# mdriver.net
KiCad netlist of a schematic drawn in Altium Designer
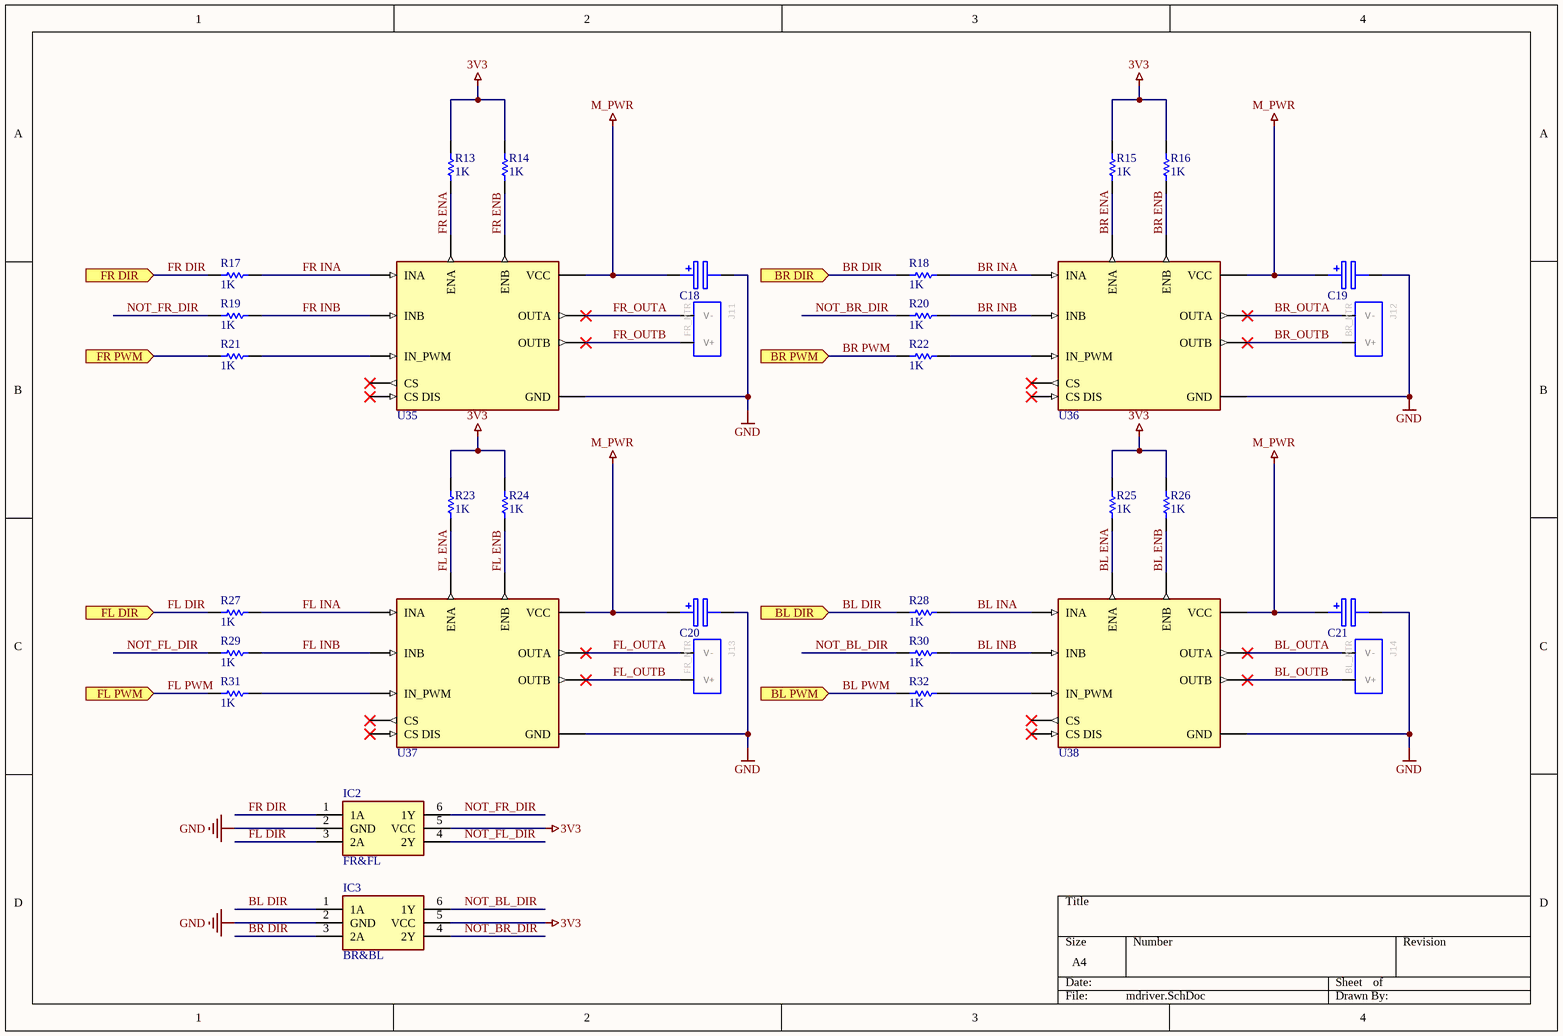
[diagram p0: mdriver.SchDoc]

(export (version "E")
  (design (tool "Eeschema 10.0.6"))
  (components
    (comp (ref "C18")
      (value "47u")
      (footprint "EEE0JA331XP")
      (description "Cap Aluminum Lytic 47uF 50V 20% (6.3 X 7.7mm) SMD 63mA 2000h 105C Automotive T/R")
      (fields
        (field (name "MOUSER PART NUMBER") "667-EEE-HBH470YAP")
        (field (name "ARROW PART NUMBER") "EEE-HBH470YAP")
      )
      (libsource (lib "Hwa Chong Institution") (part "EEE-HBH470YAP"))
    )
    (comp (ref "C19")
      (value "47u")
      (footprint "EEE0JA331XP")
      (description "Cap Aluminum Lytic 47uF 50V 20% (6.3 X 7.7mm) SMD 63mA 2000h 105C Automotive T/R")
      (fields
        (field (name "MOUSER PART NUMBER") "667-EEE-HBH470YAP")
        (field (name "ARROW PART NUMBER") "EEE-HBH470YAP")
      )
      (libsource (lib "Hwa Chong Institution") (part "EEE-HBH470YAP"))
    )
    (comp (ref "C20")
      (value "47u")
      (footprint "EEE0JA331XP")
      (description "Cap Aluminum Lytic 47uF 50V 20% (6.3 X 7.7mm) SMD 63mA 2000h 105C Automotive T/R")
      (fields
        (field (name "MOUSER PART NUMBER") "667-EEE-HBH470YAP")
        (field (name "ARROW PART NUMBER") "EEE-HBH470YAP")
      )
      (libsource (lib "Hwa Chong Institution") (part "EEE-HBH470YAP"))
    )
    (comp (ref "C21")
      (value "47u")
      (footprint "EEE0JA331XP")
      (description "Cap Aluminum Lytic 47uF 50V 20% (6.3 X 7.7mm) SMD 63mA 2000h 105C Automotive T/R")
      (fields
        (field (name "MOUSER PART NUMBER") "667-EEE-HBH470YAP")
        (field (name "ARROW PART NUMBER") "EEE-HBH470YAP")
      )
      (libsource (lib "Hwa Chong Institution") (part "EEE-HBH470YAP"))
    )
    (comp (ref "IC2")
      (value "FR&FL")
      (footprint "SOT-23-6")
      (description "Integrated Circuit")
      (fields
        (field (name "MOUSER PART NUMBER") "595-SN74LVC2G04DRLR")
        (field (name "MANUFACTURER_PART_NUMBER") "SN74LVC2G04DRLR")
      )
      (libsource (lib "Integrated_Library1") (part "SN74LVC2G04DRLR"))
    )
    (comp (ref "IC3")
      (value "BR&BL")
      (footprint "SOT-23-6")
      (description "Integrated Circuit")
      (fields
        (field (name "MOUSER PART NUMBER") "595-SN74LVC2G04DRLR")
        (field (name "MANUFACTURER_PART_NUMBER") "SN74LVC2G04DRLR")
      )
      (libsource (lib "Integrated_Library1") (part "SN74LVC2G04DRLR"))
    )
    (comp (ref "J11")
      (value "FR_MTR")
      (footprint "XT30PB-F")
      (libsource (lib "Integrated_Library1") (part "XT30PB-F"))
    )
    (comp (ref "J12")
      (value "BR_MTR")
      (footprint "XT30PB-F")
      (libsource (lib "Integrated_Library1") (part "XT30PB-F"))
    )
    (comp (ref "J13")
      (value "FR_MTR")
      (footprint "XT30PB-F")
      (libsource (lib "Integrated_Library1") (part "XT30PB-F"))
    )
    (comp (ref "J14")
      (value "BL_MTR")
      (footprint "XT30PB-F")
      (libsource (lib "Integrated_Library1") (part "XT30PB-F"))
    )
    (comp (ref "R13")
      (value "1K")
      (footprint "RES0603")
      (description "Resistor")
      (libsource (lib "Integrated_Library1") (part "RES0603"))
    )
    (comp (ref "R14")
      (value "1K")
      (footprint "RES0603")
      (description "Resistor")
      (libsource (lib "Integrated_Library1") (part "RES0603"))
    )
    (comp (ref "R15")
      (value "1K")
      (footprint "RES0603")
      (description "Resistor")
      (libsource (lib "Integrated_Library1") (part "RES0603"))
    )
    (comp (ref "R16")
      (value "1K")
      (footprint "RES0603")
      (description "Resistor")
      (libsource (lib "Integrated_Library1") (part "RES0603"))
    )
    (comp (ref "R17")
      (value "1K")
      (footprint "RES0603")
      (description "Resistor")
      (libsource (lib "Integrated_Library1") (part "RES0603"))
    )
    (comp (ref "R18")
      (value "1K")
      (footprint "RES0603")
      (description "Resistor")
      (libsource (lib "Integrated_Library1") (part "RES0603"))
    )
    (comp (ref "R19")
      (value "1K")
      (footprint "RES0603")
      (description "Resistor")
      (libsource (lib "Integrated_Library1") (part "RES0603"))
    )
    (comp (ref "R20")
      (value "1K")
      (footprint "RES0603")
      (description "Resistor")
      (libsource (lib "Integrated_Library1") (part "RES0603"))
    )
    (comp (ref "R21")
      (value "1K")
      (footprint "RES0603")
      (description "Resistor")
      (libsource (lib "Integrated_Library1") (part "RES0603"))
    )
    (comp (ref "R22")
      (value "1K")
      (footprint "RES0603")
      (description "Resistor")
      (libsource (lib "Integrated_Library1") (part "RES0603"))
    )
    (comp (ref "R23")
      (value "1K")
      (footprint "RES0603")
      (description "Resistor")
      (libsource (lib "Integrated_Library1") (part "RES0603"))
    )
    (comp (ref "R24")
      (value "1K")
      (footprint "RES0603")
      (description "Resistor")
      (libsource (lib "Integrated_Library1") (part "RES0603"))
    )
    (comp (ref "R25")
      (value "1K")
      (footprint "RES0603")
      (description "Resistor")
      (libsource (lib "Integrated_Library1") (part "RES0603"))
    )
    (comp (ref "R26")
      (value "1K")
      (footprint "RES0603")
      (description "Resistor")
      (libsource (lib "Integrated_Library1") (part "RES0603"))
    )
    (comp (ref "R27")
      (value "1K")
      (footprint "RES0603")
      (description "Resistor")
      (libsource (lib "Integrated_Library1") (part "RES0603"))
    )
    (comp (ref "R28")
      (value "1K")
      (footprint "RES0603")
      (description "Resistor")
      (libsource (lib "Integrated_Library1") (part "RES0603"))
    )
    (comp (ref "R29")
      (value "1K")
      (footprint "RES0603")
      (description "Resistor")
      (libsource (lib "Integrated_Library1") (part "RES0603"))
    )
    (comp (ref "R30")
      (value "1K")
      (footprint "RES0603")
      (description "Resistor")
      (libsource (lib "Integrated_Library1") (part "RES0603"))
    )
    (comp (ref "R31")
      (value "1K")
      (footprint "RES0603")
      (description "Resistor")
      (libsource (lib "Integrated_Library1") (part "RES0603"))
    )
    (comp (ref "R32")
      (value "1K")
      (footprint "RES0603")
      (description "Resistor")
      (libsource (lib "Integrated_Library1") (part "RES0603"))
    )
    (comp (ref "U35")
      (value "FR")
      (footprint "SOP50P1030X247-39N")
      (description "Motor Driver Power MOSFET Parallel, PWM PowerSSO-36")
      (fields (field (name "MF") "STMicroelectronics") (field (name "MP") "VNH5050A-E"))
      (libsource (lib "Integrated_Library1") (part "VNH5050A-E"))
    )
    (comp (ref "U36")
      (value "BR")
      (footprint "SOP50P1030X247-39N")
      (description "Motor Driver Power MOSFET Parallel, PWM PowerSSO-36")
      (fields (field (name "MF") "STMicroelectronics") (field (name "MP") "VNH5050A-E"))
      (libsource (lib "Integrated_Library1") (part "VNH5050A-E"))
    )
    (comp (ref "U37")
      (value "FL")
      (footprint "SOP50P1030X247-39N")
      (description "Motor Driver Power MOSFET Parallel, PWM PowerSSO-36")
      (fields (field (name "MF") "STMicroelectronics") (field (name "MP") "VNH5050A-E"))
      (libsource (lib "Integrated_Library1") (part "VNH5050A-E"))
    )
    (comp (ref "U38")
      (value "BL")
      (footprint "SOP50P1030X247-39N")
      (description "Motor Driver Power MOSFET Parallel, PWM PowerSSO-36")
      (fields (field (name "MF") "STMicroelectronics") (field (name "MP") "VNH5050A-E"))
      (libsource (lib "Integrated_Library1") (part "VNH5050A-E"))
    )
  )
  (nets
    (net (code "1") (name "/BL DIR") (class "Default")
      (node (ref "IC3") (pin "1") (pinfunction "1A_1") (pintype "passive"))
      (node (ref "R28") (pin "2") (pinfunction "2_2") (pintype "passive"))
    )
    (net (code "2") (name "/BL ENA") (class "Default")
      (node (ref "R25") (pin "1") (pinfunction "1_1") (pintype "passive"))
      (node (ref "U38") (pin "16") (pinfunction "ENA_16") (pintype "output"))
    )
    (net (code "3") (name "/BL ENB") (class "Default")
      (node (ref "R26") (pin "1") (pinfunction "1_1") (pintype "passive"))
      (node (ref "U38") (pin "21") (pinfunction "ENB_21") (pintype "output"))
    )
    (net (code "4") (name "/BL INA") (class "Default")
      (node (ref "R28") (pin "1") (pinfunction "1_1") (pintype "passive"))
      (node (ref "U38") (pin "15") (pinfunction "INA_15") (pintype "input"))
    )
    (net (code "5") (name "/BL INB") (class "Default")
      (node (ref "R30") (pin "1") (pinfunction "1_1") (pintype "passive"))
      (node (ref "U38") (pin "22") (pinfunction "INB_22") (pintype "input"))
    )
    (net (code "6") (name "/BL PWM") (class "Default")
      (node (ref "R32") (pin "2") (pinfunction "2_2") (pintype "passive"))
    )
    (net (code "7") (name "/BL_OUTA") (class "Default")
      (node (ref "J14") (pin "-") (pinfunction "V-_-") (pintype "power_in"))
      (node (ref "U38") (pin "38") (pinfunction "OUTA_38") (pintype "output"))
    )
    (net (code "8") (name "/BL_OUTB") (class "Default")
      (node (ref "J14") (pin "+") (pinfunction "V+_+") (pintype "power_in"))
      (node (ref "U38") (pin "37") (pinfunction "OUTB_37") (pintype "output"))
    )
    (net (code "9") (name "/BR DIR") (class "Default")
      (node (ref "IC3") (pin "3") (pinfunction "2A_3") (pintype "passive"))
      (node (ref "R18") (pin "2") (pinfunction "2_2") (pintype "passive"))
    )
    (net (code "10") (name "/BR ENA") (class "Default")
      (node (ref "R15") (pin "1") (pinfunction "1_1") (pintype "passive"))
      (node (ref "U36") (pin "16") (pinfunction "ENA_16") (pintype "output"))
    )
    (net (code "11") (name "/BR ENB") (class "Default")
      (node (ref "R16") (pin "1") (pinfunction "1_1") (pintype "passive"))
      (node (ref "U36") (pin "21") (pinfunction "ENB_21") (pintype "output"))
    )
    (net (code "12") (name "/BR INA") (class "Default")
      (node (ref "R18") (pin "1") (pinfunction "1_1") (pintype "passive"))
      (node (ref "U36") (pin "15") (pinfunction "INA_15") (pintype "input"))
    )
    (net (code "13") (name "/BR INB") (class "Default")
      (node (ref "R20") (pin "1") (pinfunction "1_1") (pintype "passive"))
      (node (ref "U36") (pin "22") (pinfunction "INB_22") (pintype "input"))
    )
    (net (code "14") (name "/BR PWM") (class "Default")
      (node (ref "R22") (pin "2") (pinfunction "2_2") (pintype "passive"))
    )
    (net (code "15") (name "/BR_OUTA") (class "Default")
      (node (ref "J12") (pin "-") (pinfunction "V-_-") (pintype "power_in"))
      (node (ref "U36") (pin "38") (pinfunction "OUTA_38") (pintype "output"))
    )
    (net (code "16") (name "/BR_OUTB") (class "Default")
      (node (ref "J12") (pin "+") (pinfunction "V+_+") (pintype "power_in"))
      (node (ref "U36") (pin "37") (pinfunction "OUTB_37") (pintype "output"))
    )
    (net (code "17") (name "/FL DIR") (class "Default")
      (node (ref "IC2") (pin "3") (pinfunction "2A_3") (pintype "passive"))
      (node (ref "R27") (pin "2") (pinfunction "2_2") (pintype "passive"))
    )
    (net (code "18") (name "/FL ENA") (class "Default")
      (node (ref "R23") (pin "1") (pinfunction "1_1") (pintype "passive"))
      (node (ref "U37") (pin "16") (pinfunction "ENA_16") (pintype "output"))
    )
    (net (code "19") (name "/FL ENB") (class "Default")
      (node (ref "R24") (pin "1") (pinfunction "1_1") (pintype "passive"))
      (node (ref "U37") (pin "21") (pinfunction "ENB_21") (pintype "output"))
    )
    (net (code "20") (name "/FL INA") (class "Default")
      (node (ref "R27") (pin "1") (pinfunction "1_1") (pintype "passive"))
      (node (ref "U37") (pin "15") (pinfunction "INA_15") (pintype "input"))
    )
    (net (code "21") (name "/FL INB") (class "Default")
      (node (ref "R29") (pin "1") (pinfunction "1_1") (pintype "passive"))
      (node (ref "U37") (pin "22") (pinfunction "INB_22") (pintype "input"))
    )
    (net (code "22") (name "/FL PWM") (class "Default")
      (node (ref "R31") (pin "2") (pinfunction "2_2") (pintype "passive"))
    )
    (net (code "23") (name "/FL_OUTA") (class "Default")
      (node (ref "J13") (pin "-") (pinfunction "V-_-") (pintype "power_in"))
      (node (ref "U37") (pin "38") (pinfunction "OUTA_38") (pintype "output"))
    )
    (net (code "24") (name "/FL_OUTB") (class "Default")
      (node (ref "J13") (pin "+") (pinfunction "V+_+") (pintype "power_in"))
      (node (ref "U37") (pin "37") (pinfunction "OUTB_37") (pintype "output"))
    )
    (net (code "25") (name "/FR DIR") (class "Default")
      (node (ref "IC2") (pin "1") (pinfunction "1A_1") (pintype "passive"))
      (node (ref "R17") (pin "2") (pinfunction "2_2") (pintype "passive"))
    )
    (net (code "26") (name "/FR ENA") (class "Default")
      (node (ref "R13") (pin "1") (pinfunction "1_1") (pintype "passive"))
      (node (ref "U35") (pin "16") (pinfunction "ENA_16") (pintype "output"))
    )
    (net (code "27") (name "/FR ENB") (class "Default")
      (node (ref "R14") (pin "1") (pinfunction "1_1") (pintype "passive"))
      (node (ref "U35") (pin "21") (pinfunction "ENB_21") (pintype "output"))
    )
    (net (code "28") (name "/FR INA") (class "Default")
      (node (ref "R17") (pin "1") (pinfunction "1_1") (pintype "passive"))
      (node (ref "U35") (pin "15") (pinfunction "INA_15") (pintype "input"))
    )
    (net (code "29") (name "/FR INB") (class "Default")
      (node (ref "R19") (pin "1") (pinfunction "1_1") (pintype "passive"))
      (node (ref "U35") (pin "22") (pinfunction "INB_22") (pintype "input"))
    )
    (net (code "30") (name "/FR PWM") (class "Default")
      (node (ref "R21") (pin "2") (pinfunction "2_2") (pintype "passive"))
    )
    (net (code "31") (name "/FR_OUTA") (class "Default")
      (node (ref "J11") (pin "-") (pinfunction "V-_-") (pintype "power_in"))
      (node (ref "U35") (pin "38") (pinfunction "OUTA_38") (pintype "output"))
    )
    (net (code "32") (name "/FR_OUTB") (class "Default")
      (node (ref "J11") (pin "+") (pinfunction "V+_+") (pintype "power_in"))
      (node (ref "U35") (pin "37") (pinfunction "OUTB_37") (pintype "output"))
    )
    (net (code "33") (name "/NOT_BL_DIR") (class "Default")
      (node (ref "IC3") (pin "6") (pinfunction "1Y_6") (pintype "passive"))
      (node (ref "R30") (pin "2") (pinfunction "2_2") (pintype "passive"))
    )
    (net (code "34") (name "/NOT_BR_DIR") (class "Default")
      (node (ref "IC3") (pin "4") (pinfunction "2Y_4") (pintype "passive"))
      (node (ref "R20") (pin "2") (pinfunction "2_2") (pintype "passive"))
    )
    (net (code "35") (name "/NOT_FL_DIR") (class "Default")
      (node (ref "IC2") (pin "4") (pinfunction "2Y_4") (pintype "passive"))
      (node (ref "R29") (pin "2") (pinfunction "2_2") (pintype "passive"))
    )
    (net (code "36") (name "/NOT_FR_DIR") (class "Default")
      (node (ref "IC2") (pin "6") (pinfunction "1Y_6") (pintype "passive"))
      (node (ref "R19") (pin "2") (pinfunction "2_2") (pintype "passive"))
    )
    (net (code "37") (name "3V3") (class "Default")
      (node (ref "IC2") (pin "5") (pinfunction "VCC_5") (pintype "passive"))
      (node (ref "IC3") (pin "5") (pinfunction "VCC_5") (pintype "passive"))
      (node (ref "R13") (pin "2") (pinfunction "2_2") (pintype "passive"))
      (node (ref "R14") (pin "2") (pinfunction "2_2") (pintype "passive"))
      (node (ref "R15") (pin "2") (pinfunction "2_2") (pintype "passive"))
      (node (ref "R16") (pin "2") (pinfunction "2_2") (pintype "passive"))
      (node (ref "R23") (pin "2") (pinfunction "2_2") (pintype "passive"))
      (node (ref "R24") (pin "2") (pinfunction "2_2") (pintype "passive"))
      (node (ref "R25") (pin "2") (pinfunction "2_2") (pintype "passive"))
      (node (ref "R26") (pin "2") (pinfunction "2_2") (pintype "passive"))
    )
    (net (code "38") (name "GND") (class "Default")
      (node (ref "C18") (pin "2") (pinfunction "-_2") (pintype "passive"))
      (node (ref "C19") (pin "2") (pinfunction "-_2") (pintype "passive"))
      (node (ref "C20") (pin "2") (pinfunction "-_2") (pintype "passive"))
      (node (ref "C21") (pin "2") (pinfunction "-_2") (pintype "passive"))
      (node (ref "IC2") (pin "2") (pinfunction "GND_2") (pintype "passive"))
      (node (ref "IC3") (pin "2") (pinfunction "GND_2") (pintype "passive"))
      (node (ref "U35") (pin "GND") (pinfunction "GND_GND") (pintype "power_in"))
      (node (ref "U36") (pin "GND") (pinfunction "GND_GND") (pintype "power_in"))
      (node (ref "U37") (pin "GND") (pinfunction "GND_GND") (pintype "power_in"))
      (node (ref "U38") (pin "GND") (pinfunction "GND_GND") (pintype "power_in"))
    )
    (net (code "39") (name "M_PWR") (class "Default")
      (node (ref "C18") (pin "1") (pinfunction "+_1") (pintype "passive"))
      (node (ref "C19") (pin "1") (pinfunction "+_1") (pintype "passive"))
      (node (ref "C20") (pin "1") (pinfunction "+_1") (pintype "passive"))
      (node (ref "C21") (pin "1") (pinfunction "+_1") (pintype "passive"))
      (node (ref "U35") (pin "39") (pinfunction "VCC_39") (pintype "power_in"))
      (node (ref "U36") (pin "39") (pinfunction "VCC_39") (pintype "power_in"))
      (node (ref "U37") (pin "39") (pinfunction "VCC_39") (pintype "power_in"))
      (node (ref "U38") (pin "39") (pinfunction "VCC_39") (pintype "power_in"))
    )
    (net (code "40") (name "Net-(U35-IN_PWM)") (class "Default")
      (node (ref "R21") (pin "1") (pinfunction "1_1") (pintype "passive"))
      (node (ref "U35") (pin "17") (pinfunction "IN_PWM_17") (pintype "input"))
    )
    (net (code "41") (name "Net-(U36-IN_PWM)") (class "Default")
      (node (ref "R22") (pin "1") (pinfunction "1_1") (pintype "passive"))
      (node (ref "U36") (pin "17") (pinfunction "IN_PWM_17") (pintype "input"))
    )
    (net (code "42") (name "Net-(U37-IN_PWM)") (class "Default")
      (node (ref "R31") (pin "1") (pinfunction "1_1") (pintype "passive"))
      (node (ref "U37") (pin "17") (pinfunction "IN_PWM_17") (pintype "input"))
    )
    (net (code "43") (name "Net-(U38-IN_PWM)") (class "Default")
      (node (ref "R32") (pin "1") (pinfunction "1_1") (pintype "passive"))
      (node (ref "U38") (pin "17") (pinfunction "IN_PWM_17") (pintype "input"))
    )
    (net (code "44") (name "unconnected-(U35-PadCS)") (class "Default")
      (node (ref "U35") (pin "CS") (pinfunction "CS_CS") (pintype "output+no_connect"))
    )
    (net (code "45") (name "unconnected-(U35-PadCS_DIS)") (class "Default")
      (node (ref "U35") (pin "CS_DIS") (pinfunction "CS_DIS_CS_DIS") (pintype "input+no_connect"))
    )
    (net (code "46") (name "unconnected-(U36-PadCS)") (class "Default")
      (node (ref "U36") (pin "CS") (pinfunction "CS_CS") (pintype "output+no_connect"))
    )
    (net (code "47") (name "unconnected-(U36-PadCS_DIS)") (class "Default")
      (node (ref "U36") (pin "CS_DIS") (pinfunction "CS_DIS_CS_DIS") (pintype "input+no_connect"))
    )
    (net (code "48") (name "unconnected-(U37-PadCS)") (class "Default")
      (node (ref "U37") (pin "CS") (pinfunction "CS_CS") (pintype "output+no_connect"))
    )
    (net (code "49") (name "unconnected-(U37-PadCS_DIS)") (class "Default")
      (node (ref "U37") (pin "CS_DIS") (pinfunction "CS_DIS_CS_DIS") (pintype "input+no_connect"))
    )
    (net (code "50") (name "unconnected-(U38-PadCS)") (class "Default")
      (node (ref "U38") (pin "CS") (pinfunction "CS_CS") (pintype "output+no_connect"))
    )
    (net (code "51") (name "unconnected-(U38-PadCS_DIS)") (class "Default")
      (node (ref "U38") (pin "CS_DIS") (pinfunction "CS_DIS_CS_DIS") (pintype "input+no_connect"))
    )
  )
)
